# Joe_final_hack4.net
KiCad netlist of a schematic drawn in EAGLE
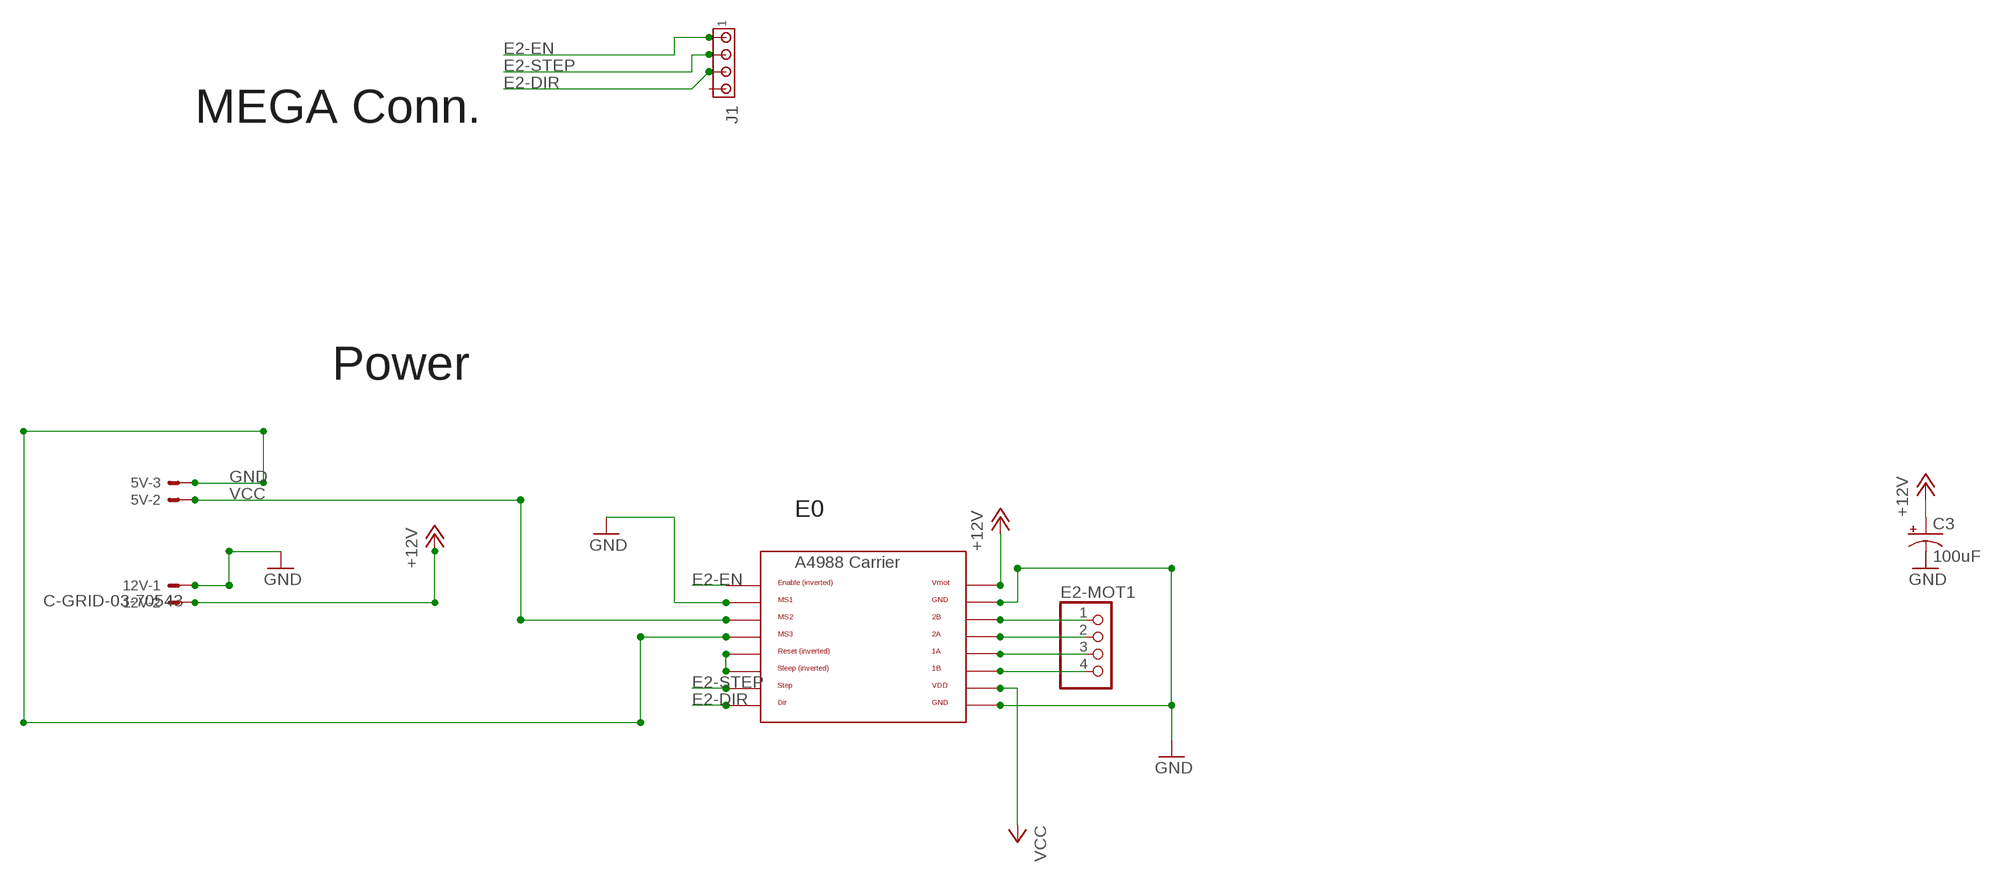
[diagram p0: schematic, sheet 1]

(export (version "E")
  (design (tool "Eeschema 10.0.6"))
  (components
    (comp (ref "5V")
      (value "C-GRID-03-70543")
      (footprint "eagle-import:70543-03")
      (libsource (lib "eagle-import") (part "C-GRID-03-70543"))
    )
    (comp (ref "12V")
      (value "C-GRID-03-70543")
      (footprint "eagle-import:70543-03")
      (libsource (lib "eagle-import") (part "C-GRID-03-70543"))
    )
    (comp (ref "C3")
      (value "100uF")
      (footprint "eagle-import:153CLV-0605")
      (libsource (lib "eagle-import") (part "CPOL-US153CLV-0605"))
    )
    (comp (ref "E2-MOT1")
      (value "PINHD-1X4")
      (footprint "eagle-import:1X04")
      (libsource (lib "eagle-import") (part "PINHD-1X4"))
    )
    (comp (ref "J1")
      (value "MTA04-156")
      (footprint "eagle-import:1X4MTA")
      (libsource (lib "eagle-import") (part "MTA04-156"))
    )
    (comp (ref "U$4")
      (value "A4988BREAKOUT")
      (footprint "eagle-import:A4988BREAKOUT")
      (libsource (lib "eagle-import") (part "A4988BREAKOUT"))
    )
  )
  (nets
    (net (code "1") (name "+12V") (class "Default")
      (node (ref "12V") (pin "2") (pinfunction "S_2") (pintype "passive"))
      (node (ref "C3") (pin "+") (pinfunction "+_+") (pintype "passive"))
      (node (ref "U$4") (pin "VMOT") (pinfunction "VMOT_VMOT") (pintype "power_in"))
    )
    (net (code "2") (name "/E2-DIR") (class "Default")
      (node (ref "J1") (pin "3") (pinfunction "3_3") (pintype "passive"))
      (node (ref "U$4") (pin "DIR") (pinfunction "DIR_DIR") (pintype "input"))
    )
    (net (code "3") (name "/E2-EN") (class "Default")
      (node (ref "J1") (pin "1") (pinfunction "1_1") (pintype "passive"))
      (node (ref "U$4") (pin "EN") (pinfunction "EN_EN") (pintype "input"))
    )
    (net (code "4") (name "/E2-STEP") (class "Default")
      (node (ref "J1") (pin "2") (pinfunction "2_2") (pintype "passive"))
      (node (ref "U$4") (pin "STEP") (pinfunction "STEP_STEP") (pintype "input"))
    )
    (net (code "5") (name "GND") (class "Default")
      (node (ref "12V") (pin "1") (pinfunction "S_1") (pintype "passive"))
      (node (ref "5V") (pin "3") (pinfunction "S_3") (pintype "passive"))
      (node (ref "C3") (pin "-") (pinfunction "-_-") (pintype "passive"))
      (node (ref "U$4") (pin "GND") (pinfunction "GND_GND") (pintype "power_in"))
      (node (ref "U$4") (pin "GND@0") (pinfunction "GND_GND@0") (pintype "power_in"))
      (node (ref "U$4") (pin "MS1") (pinfunction "MS1_MS1") (pintype "input"))
      (node (ref "U$4") (pin "MS3") (pinfunction "MS3_MS3") (pintype "input"))
    )
    (net (code "6") (name "Net-(E2-MOT1-Pad1)") (class "Default")
      (node (ref "E2-MOT1") (pin "1") (pinfunction "1_1") (pintype "passive"))
      (node (ref "U$4") (pin "2B") (pinfunction "2B_2B") (pintype "output"))
    )
    (net (code "7") (name "Net-(E2-MOT1-Pad2)") (class "Default")
      (node (ref "E2-MOT1") (pin "2") (pinfunction "2_2") (pintype "passive"))
      (node (ref "U$4") (pin "2A") (pinfunction "2A_2A") (pintype "output"))
    )
    (net (code "8") (name "Net-(E2-MOT1-Pad3)") (class "Default")
      (node (ref "E2-MOT1") (pin "3") (pinfunction "3_3") (pintype "passive"))
      (node (ref "U$4") (pin "1A") (pinfunction "1A_1A") (pintype "output"))
    )
    (net (code "9") (name "Net-(E2-MOT1-Pad4)") (class "Default")
      (node (ref "E2-MOT1") (pin "4") (pinfunction "4_4") (pintype "passive"))
      (node (ref "U$4") (pin "1B") (pinfunction "1B_1B") (pintype "output"))
    )
    (net (code "10") (name "Net-(U$4-SLEEP)") (class "Default")
      (node (ref "U$4") (pin "RST") (pinfunction "RST_RST") (pintype "input"))
      (node (ref "U$4") (pin "SLP") (pinfunction "SLEEP_SLP") (pintype "input"))
    )
    (net (code "11") (name "VCC") (class "Default")
      (node (ref "5V") (pin "2") (pinfunction "S_2") (pintype "passive"))
      (node (ref "U$4") (pin "MS2") (pinfunction "MS2_MS2") (pintype "input"))
      (node (ref "U$4") (pin "VDD") (pinfunction "VDD_VDD") (pintype "power_in"))
    )
    (net (code "12") (name "unconnected-(J1-Pad4)") (class "Default")
      (node (ref "J1") (pin "4") (pinfunction "4_4") (pintype "passive"))
    )
  )
)
